# DRIVER.net
KiCad netlist of a schematic drawn in Altium Designer
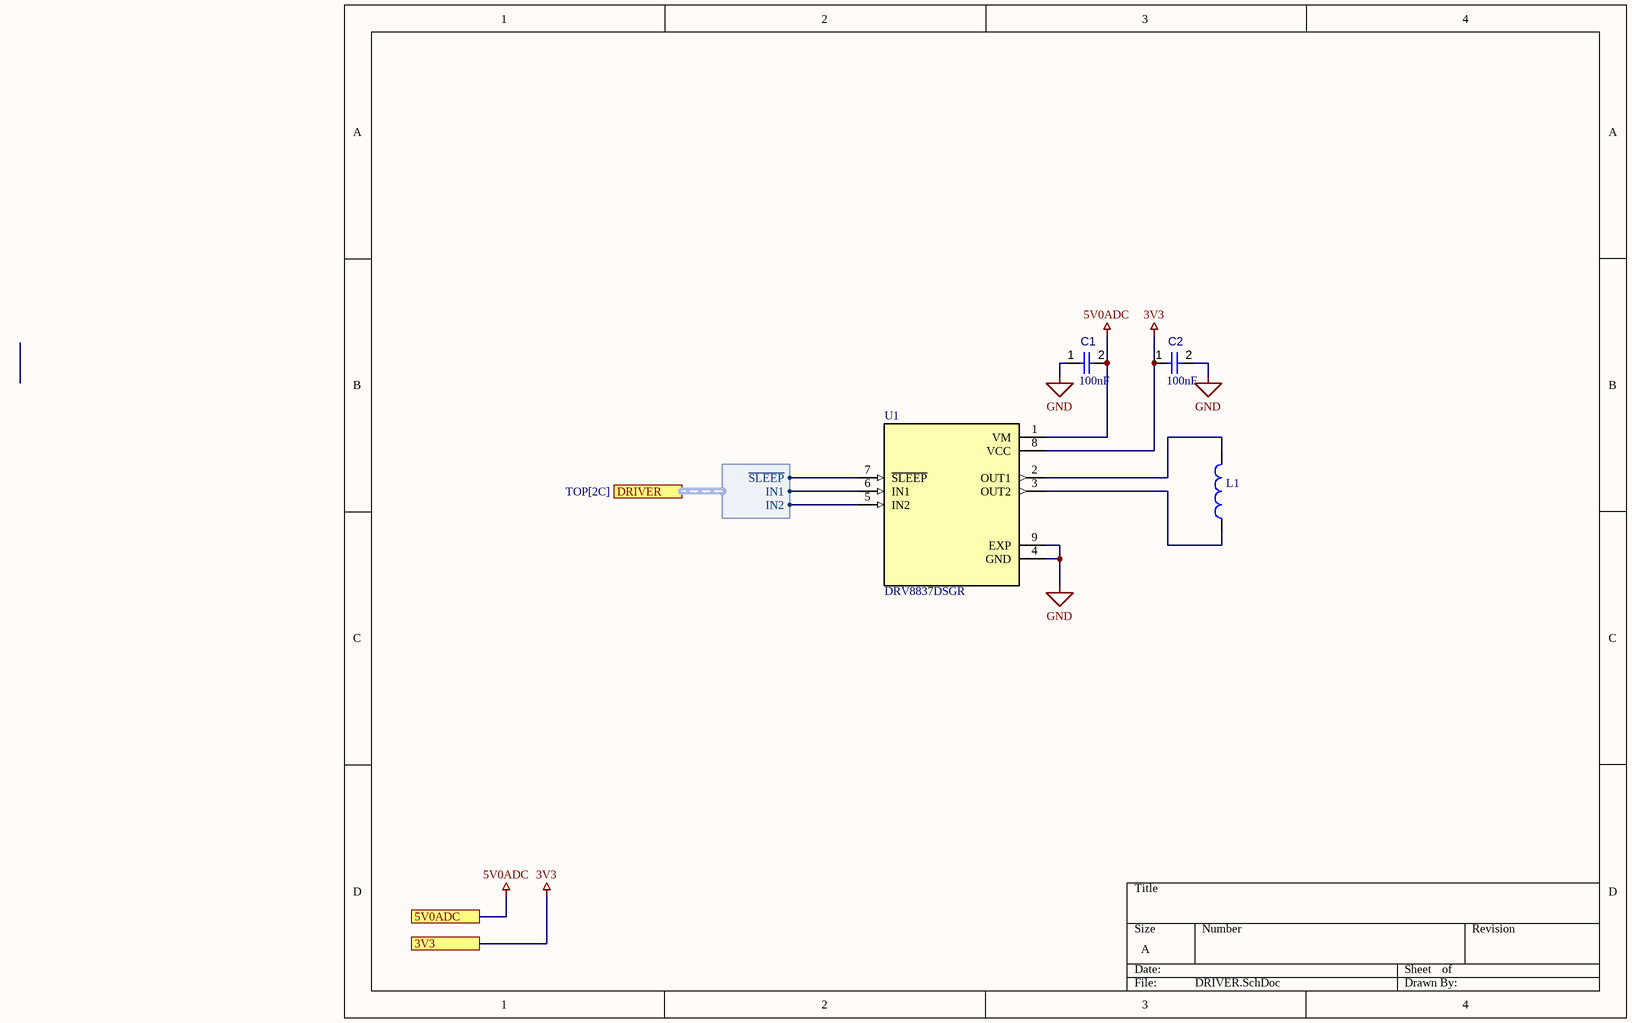
[diagram p0: DRIVER.SchDoc]

(export (version "E")
  (design (tool "Eeschema 10.0.6"))
  (components
    (comp (ref "C1")
      (value "100nF")
      (footprint "CAPC1005X56X25LL10T15")
      (description "Chip Capacitor, 0.1 uF, +/- 5%, 16 V, 0402 (1005 Metric)")
      (fields (field (name "TOLERANCE") "5%") (field (name "Comment") "Capacitor 0.1 uF +/- 5% 16 V 0402"))
      (libsource (lib "Altium Default Library") (part "CAP-NP-2"))
    )
    (comp (ref "C2")
      (value "100nF")
      (footprint "CAPC1005X56X25LL10T15")
      (description "Chip Capacitor, 0.1 uF, +/- 5%, 16 V, 0402 (1005 Metric)")
      (fields (field (name "TOLERANCE") "5%") (field (name "Comment") "Capacitor 0.1 uF +/- 5% 16 V 0402"))
      (libsource (lib "Altium Default Library") (part "CAP-NP-2"))
    )
    (comp (ref "L1") (value "Inductors") (libsource (lib "Altium Default Library") (part "IND-2")))
    (comp (ref "U1")
      (value "DRV8837DSGR")
      (footprint "SON50P200X200X80-9N")
      (description "11-V, 1.8-A H-bridge motor driver 8-WSON -40 to 85")
      (fields
        (field (name "MF") "Texas Instruments")
        (field (name "BUYPART") "https://www.snapeda.com/parts/DRV8837DSGR/Texas%20Instruments/view-part/230051/?ref=eda")
      )
      (libsource (lib "Altium Default Library") (part "DRV8837DSGR"))
    )
  )
  (nets
    (net (code "2") (name "/IN1") (class "Default")
      (node (ref "U1") (pin "6") (pinfunction "IN1_6") (pintype "input"))
    )
    (net (code "3") (name "/IN2") (class "Default")
      (node (ref "U1") (pin "5") (pinfunction "IN2_5") (pintype "input"))
    )
    (net (code "5") (name "/~{SLEEP}") (class "Default")
      (node (ref "U1") (pin "7") (pinfunction "~{SLEEP}_7") (pintype "input"))
    )
    (net (code "6") (name "3V3") (class "Default")
      (node (ref "C2") (pin "1") (pinfunction "1_1") (pintype "passive"))
      (node (ref "U1") (pin "8") (pinfunction "VCC_8") (pintype "power_in"))
    )
    (net (code "7") (name "5V0ADC") (class "Default")
      (node (ref "C1") (pin "2") (pinfunction "2_2") (pintype "passive"))
      (node (ref "U1") (pin "1") (pinfunction "VM_1") (pintype "power_in"))
    )
    (net (code "8") (name "GND") (class "Default")
      (node (ref "C1") (pin "1") (pinfunction "1_1") (pintype "passive"))
      (node (ref "C2") (pin "2") (pinfunction "2_2") (pintype "passive"))
      (node (ref "U1") (pin "4") (pinfunction "GND_4") (pintype "power_in"))
      (node (ref "U1") (pin "9") (pinfunction "EXP_9") (pintype "power_in"))
    )
    (net (code "9") (name "Net-(U1-OUT1)") (class "Default")
      (node (ref "L1") (pin "2") (pinfunction "2_2") (pintype "passive"))
      (node (ref "U1") (pin "2") (pinfunction "OUT1_2") (pintype "output"))
    )
    (net (code "10") (name "Net-(U1-OUT2)") (class "Default")
      (node (ref "L1") (pin "1") (pinfunction "1_1") (pintype "passive"))
      (node (ref "U1") (pin "3") (pinfunction "OUT2_3") (pintype "output"))
    )
  )
)
